# main-stm-03_1.net
KiCad netlist of a schematic drawn in EAGLE
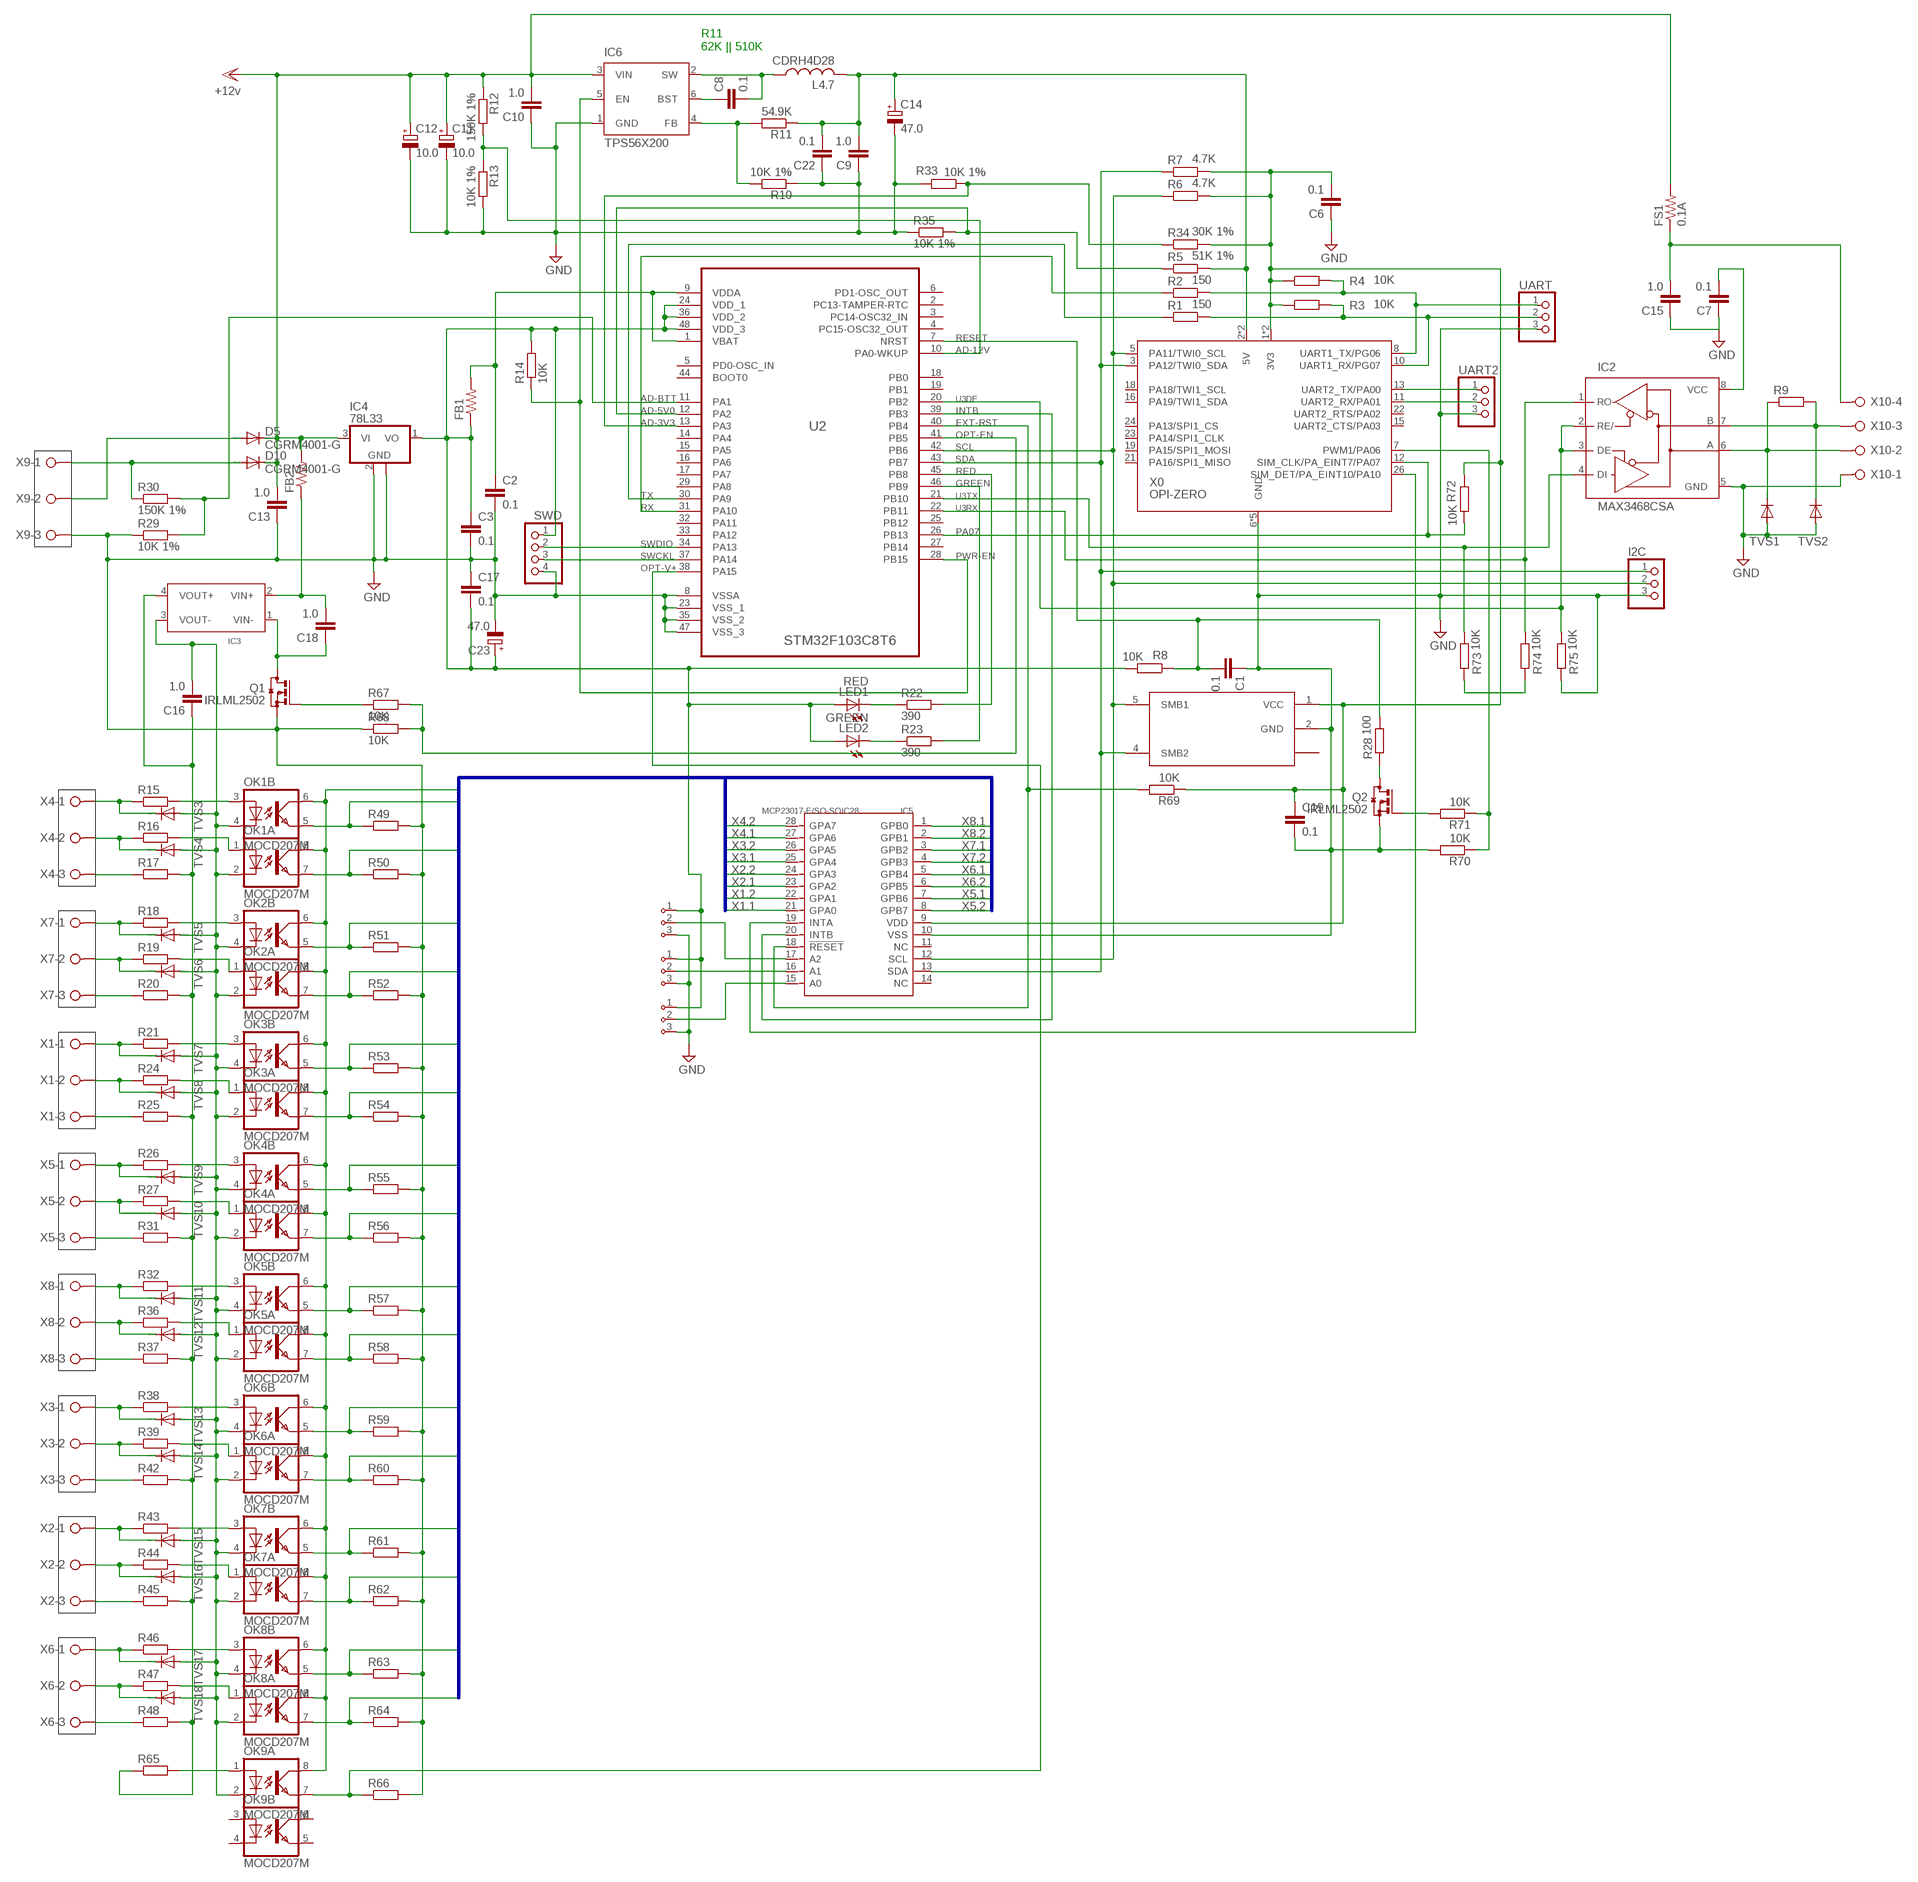
[diagram p0: schematic, sheet 1]

(export (version "E")
  (design (tool "Eeschema 10.0.6"))
  (components
    (comp (ref "A0")
      (value "ADDR3PIN0603")
      (footprint "eagle-import:0603-3PIN")
      (libsource (lib "eagle-import") (part "ADDR3PIN0603"))
    )
    (comp (ref "A1")
      (value "ADDR3PIN0603")
      (footprint "eagle-import:0603-3PIN")
      (libsource (lib "eagle-import") (part "ADDR3PIN0603"))
    )
    (comp (ref "A2")
      (value "ADDR3PIN0603")
      (footprint "eagle-import:0603-3PIN")
      (libsource (lib "eagle-import") (part "ADDR3PIN0603"))
    )
    (comp (ref "C1")
      (value "0.1")
      (footprint "eagle-import:C0603")
      (libsource (lib "eagle-import") (part "C-EUC0603"))
    )
    (comp (ref "C2")
      (value "0.1")
      (footprint "eagle-import:C0603")
      (libsource (lib "eagle-import") (part "C-EUC0603"))
    )
    (comp (ref "C3")
      (value "0.1")
      (footprint "eagle-import:C0603")
      (libsource (lib "eagle-import") (part "C-EUC0603"))
    )
    (comp (ref "C6")
      (value "0.1")
      (footprint "eagle-import:C0805")
      (libsource (lib "eagle-import") (part "C-EUC0805"))
    )
    (comp (ref "C7")
      (value "0.1")
      (footprint "eagle-import:C0805")
      (libsource (lib "eagle-import") (part "C-EUC0805"))
    )
    (comp (ref "C8")
      (value "0.1")
      (footprint "eagle-import:C0805")
      (libsource (lib "eagle-import") (part "C-EUC0805"))
    )
    (comp (ref "C9")
      (value "1.0")
      (footprint "eagle-import:C0805")
      (libsource (lib "eagle-import") (part "C-EUC0805"))
    )
    (comp (ref "C10")
      (value "1.0")
      (footprint "eagle-import:C1206")
      (libsource (lib "eagle-import") (part "C-EUC1206"))
    )
    (comp (ref "C11")
      (value "10.0")
      (footprint "eagle-import:C_6032-28R")
      (libsource (lib "eagle-import") (part "CPOL-EUC/6032-28R"))
    )
    (comp (ref "C12")
      (value "10.0")
      (footprint "eagle-import:C_6032-28R")
      (libsource (lib "eagle-import") (part "CPOL-EUC/6032-28R"))
    )
    (comp (ref "C13")
      (value "1.0")
      (footprint "eagle-import:C1206")
      (libsource (lib "eagle-import") (part "C-EUC1206"))
    )
    (comp (ref "C14")
      (value "47.0")
      (footprint "eagle-import:B_3528-21R")
      (libsource (lib "eagle-import") (part "CPOL-EUB/3528-21R"))
    )
    (comp (ref "C15")
      (value "1.0")
      (footprint "eagle-import:C1206")
      (libsource (lib "eagle-import") (part "C-EUC1206"))
    )
    (comp (ref "C16")
      (value "1.0")
      (footprint "eagle-import:C1206")
      (libsource (lib "eagle-import") (part "C-EUC1206"))
    )
    (comp (ref "C17")
      (value "0.1")
      (footprint "eagle-import:C0603")
      (libsource (lib "eagle-import") (part "C-EUC0603"))
    )
    (comp (ref "C18")
      (value "1.0")
      (footprint "eagle-import:C1206")
      (libsource (lib "eagle-import") (part "C-EUC1206"))
    )
    (comp (ref "C19")
      (value "0.1")
      (footprint "eagle-import:C0603")
      (libsource (lib "eagle-import") (part "C-EUC0603"))
    )
    (comp (ref "C22")
      (value "0.1")
      (footprint "eagle-import:C0805")
      (libsource (lib "eagle-import") (part "C-EUC0805"))
    )
    (comp (ref "C23")
      (value "47.0")
      (footprint "eagle-import:B_3528-21R")
      (libsource (lib "eagle-import") (part "CPOL-EUB/3528-21R"))
    )
    (comp (ref "D5")
      (value "CGRM4001-G")
      (footprint "eagle-import:SOD-123_MINI-SMA")
      (libsource (lib "eagle-import") (part "CGRM400-G1"))
    )
    (comp (ref "D10")
      (value "CGRM4001-G")
      (footprint "eagle-import:SOD-123_MINI-SMA")
      (libsource (lib "eagle-import") (part "CGRM400-G1"))
    )
    (comp (ref "FB1")
      (value "R-US_R0805")
      (footprint "eagle-import:R0805")
      (libsource (lib "eagle-import") (part "R-US_R0805"))
    )
    (comp (ref "FB2")
      (value "R-US_R1206")
      (footprint "eagle-import:R1206")
      (libsource (lib "eagle-import") (part "R-US_R1206"))
    )
    (comp (ref "FS1")
      (value "0.1A")
      (footprint "eagle-import:R1210")
      (libsource (lib "eagle-import") (part "R-US_R1210"))
    )
    (comp (ref "I2C")
      (value "PINHD-1X3")
      (footprint "eagle-import:1X03")
      (libsource (lib "eagle-import") (part "PINHD-1X3"))
    )
    (comp (ref "IC2")
      (value "MAX3468CSA")
      (footprint "eagle-import:SO08")
      (fields (field (name "MPN") "MAX3468CSA+"))
      (libsource (lib "eagle-import") (part "MAX34SA68C"))
    )
    (comp (ref "IC3")
      (value "DC-DC-CONV-4PIN-ISOLATINGMURATA-NME-05-12-SERIES")
      (footprint "eagle-import:DC-DC-MURATA-NME-05-12-SERIES")
      (libsource (lib "eagle-import") (part "DC-DC-CONV-4PIN-ISOLATINGMURATA-NME-05-12-SERIES"))
    )
    (comp (ref "IC4")
      (value "78L33")
      (footprint "eagle-import:SOT89")
      (libsource (lib "eagle-import") (part "78LF05"))
    )
    (comp (ref "IC5")
      (value "MCP23017-E/SO-SOIC28")
      (footprint "eagle-import:SOIC28-1.27-17.9X7.5MM")
      (fields (field (name "MPN") "MCP23017-E/SO"))
      (libsource (lib "eagle-import") (part "INTERFACE-MCP23017-E(SOIC28)"))
    )
    (comp (ref "IC6")
      (value "TPS56X200")
      (footprint "eagle-import:TSOT23-6_DDC")
      (libsource (lib "eagle-import") (part "TPS56X200"))
    )
    (comp (ref "IC7")
      (value "LTC1694")
      (footprint "eagle-import:SOT23-5")
      (libsource (lib "eagle-import") (part "LTC1694"))
    )
    (comp (ref "L4.7")
      (value "CDRH4D28")
      (footprint "eagle-import:CDRH4D28")
      (libsource (lib "eagle-import") (part "CDRH4D28"))
    )
    (comp (ref "LED1")
      (value "RED")
      (footprint "eagle-import:CHIPLED_1206")
      (libsource (lib "eagle-import") (part "LEDCHIPLED_1206"))
    )
    (comp (ref "LED2")
      (value "GREEN")
      (footprint "eagle-import:CHIPLED_1206")
      (libsource (lib "eagle-import") (part "LEDCHIPLED_1206"))
    )
    (comp (ref "OK1")
      (value "MOCD207M")
      (footprint "eagle-import:SOIC08-FAIRCHILD")
      (fields (field (name "MF") "FAIRCHILD SEMICONDUCTOR") (field (name "MPN") "MOCD207-M"))
      (libsource (lib "eagle-import") (part "MOCD20M7"))
    )
    (comp (ref "OK2")
      (value "MOCD207M")
      (footprint "eagle-import:SOIC08-FAIRCHILD")
      (fields (field (name "MF") "FAIRCHILD SEMICONDUCTOR") (field (name "MPN") "MOCD207-M"))
      (libsource (lib "eagle-import") (part "MOCD20M7"))
    )
    (comp (ref "OK3")
      (value "MOCD207M")
      (footprint "eagle-import:SOIC08-FAIRCHILD")
      (fields (field (name "MF") "FAIRCHILD SEMICONDUCTOR") (field (name "MPN") "MOCD207-M"))
      (libsource (lib "eagle-import") (part "MOCD20M7"))
    )
    (comp (ref "OK4")
      (value "MOCD207M")
      (footprint "eagle-import:SOIC08-FAIRCHILD")
      (fields (field (name "MF") "FAIRCHILD SEMICONDUCTOR") (field (name "MPN") "MOCD207-M"))
      (libsource (lib "eagle-import") (part "MOCD20M7"))
    )
    (comp (ref "OK5")
      (value "MOCD207M")
      (footprint "eagle-import:SOIC08-FAIRCHILD")
      (fields (field (name "MF") "FAIRCHILD SEMICONDUCTOR") (field (name "MPN") "MOCD207-M"))
      (libsource (lib "eagle-import") (part "MOCD20M7"))
    )
    (comp (ref "OK6")
      (value "MOCD207M")
      (footprint "eagle-import:SOIC08-FAIRCHILD")
      (fields (field (name "MF") "FAIRCHILD SEMICONDUCTOR") (field (name "MPN") "MOCD207-M"))
      (libsource (lib "eagle-import") (part "MOCD20M7"))
    )
    (comp (ref "OK7")
      (value "MOCD207M")
      (footprint "eagle-import:SOIC08-FAIRCHILD")
      (fields (field (name "MF") "FAIRCHILD SEMICONDUCTOR") (field (name "MPN") "MOCD207-M"))
      (libsource (lib "eagle-import") (part "MOCD20M7"))
    )
    (comp (ref "OK8")
      (value "MOCD207M")
      (footprint "eagle-import:SOIC08-FAIRCHILD")
      (fields (field (name "MF") "FAIRCHILD SEMICONDUCTOR") (field (name "MPN") "MOCD207-M"))
      (libsource (lib "eagle-import") (part "MOCD20M7"))
    )
    (comp (ref "OK9")
      (value "MOCD207M")
      (footprint "eagle-import:SOIC08-FAIRCHILD")
      (fields (field (name "MF") "FAIRCHILD SEMICONDUCTOR") (field (name "MPN") "MOCD207-M"))
      (libsource (lib "eagle-import") (part "MOCD20M7"))
    )
    (comp (ref "Q1")
      (value "IRLML2502")
      (footprint "eagle-import:SOT23")
      (libsource (lib "eagle-import") (part "IRLML2502"))
    )
    (comp (ref "Q2")
      (value "IRLML2502")
      (footprint "eagle-import:SOT23")
      (libsource (lib "eagle-import") (part "IRLML2502"))
    )
    (comp (ref "R1")
      (value "150")
      (footprint "eagle-import:R0603")
      (libsource (lib "eagle-import") (part "R-EU_R0603"))
    )
    (comp (ref "R2")
      (value "150")
      (footprint "eagle-import:R0603")
      (libsource (lib "eagle-import") (part "R-EU_R0603"))
    )
    (comp (ref "R3")
      (value "10K")
      (footprint "eagle-import:R0603")
      (libsource (lib "eagle-import") (part "R-EU_R0603"))
    )
    (comp (ref "R4")
      (value "10K")
      (footprint "eagle-import:R0603")
      (libsource (lib "eagle-import") (part "R-EU_R0603"))
    )
    (comp (ref "R5")
      (value "51K 1%")
      (footprint "eagle-import:R0603")
      (libsource (lib "eagle-import") (part "R-EU_R0603"))
    )
    (comp (ref "R6")
      (value "4.7K")
      (footprint "eagle-import:R0603")
      (libsource (lib "eagle-import") (part "R-EU_R0603"))
    )
    (comp (ref "R7")
      (value "4.7K")
      (footprint "eagle-import:R0603")
      (libsource (lib "eagle-import") (part "R-EU_R0603"))
    )
    (comp (ref "R8")
      (value "10K")
      (footprint "eagle-import:R0603")
      (libsource (lib "eagle-import") (part "R-EU_R0603"))
    )
    (comp (ref "R9")
      (value "R-EU_R1206")
      (footprint "eagle-import:R1206")
      (libsource (lib "eagle-import") (part "R-EU_R1206"))
    )
    (comp (ref "R10")
      (value "10K 1%")
      (footprint "eagle-import:R0603")
      (libsource (lib "eagle-import") (part "R-EU_R0603"))
    )
    (comp (ref "R11")
      (value "54.9K")
      (footprint "eagle-import:R0603")
      (libsource (lib "eagle-import") (part "R-EU_R0603"))
    )
    (comp (ref "R12")
      (value "150K 1%")
      (footprint "eagle-import:R0603")
      (libsource (lib "eagle-import") (part "R-EU_R0603"))
    )
    (comp (ref "R13")
      (value "10K 1%")
      (footprint "eagle-import:R0603")
      (libsource (lib "eagle-import") (part "R-EU_R0603"))
    )
    (comp (ref "R14")
      (value "10K")
      (footprint "eagle-import:R0603")
      (libsource (lib "eagle-import") (part "R-EU_R0603"))
    )
    (comp (ref "R15")
      (value "R-EU_R0603")
      (footprint "eagle-import:R0603")
      (libsource (lib "eagle-import") (part "R-EU_R0603"))
    )
    (comp (ref "R16")
      (value "R-EU_R0603")
      (footprint "eagle-import:R0603")
      (libsource (lib "eagle-import") (part "R-EU_R0603"))
    )
    (comp (ref "R17")
      (value "R-EU_R0603")
      (footprint "eagle-import:R0603")
      (libsource (lib "eagle-import") (part "R-EU_R0603"))
    )
    (comp (ref "R18")
      (value "R-EU_R0603")
      (footprint "eagle-import:R0603")
      (libsource (lib "eagle-import") (part "R-EU_R0603"))
    )
    (comp (ref "R19")
      (value "R-EU_R0603")
      (footprint "eagle-import:R0603")
      (libsource (lib "eagle-import") (part "R-EU_R0603"))
    )
    (comp (ref "R20")
      (value "R-EU_R0603")
      (footprint "eagle-import:R0603")
      (libsource (lib "eagle-import") (part "R-EU_R0603"))
    )
    (comp (ref "R21")
      (value "R-EU_R0603")
      (footprint "eagle-import:R0603")
      (libsource (lib "eagle-import") (part "R-EU_R0603"))
    )
    (comp (ref "R22")
      (value "390")
      (footprint "eagle-import:R0603")
      (libsource (lib "eagle-import") (part "R-EU_R0603"))
    )
    (comp (ref "R23")
      (value "390")
      (footprint "eagle-import:R0603")
      (libsource (lib "eagle-import") (part "R-EU_R0603"))
    )
    (comp (ref "R24")
      (value "R-EU_R0603")
      (footprint "eagle-import:R0603")
      (libsource (lib "eagle-import") (part "R-EU_R0603"))
    )
    (comp (ref "R25")
      (value "R-EU_R0603")
      (footprint "eagle-import:R0603")
      (libsource (lib "eagle-import") (part "R-EU_R0603"))
    )
    (comp (ref "R26")
      (value "R-EU_R0603")
      (footprint "eagle-import:R0603")
      (libsource (lib "eagle-import") (part "R-EU_R0603"))
    )
    (comp (ref "R27")
      (value "R-EU_R0603")
      (footprint "eagle-import:R0603")
      (libsource (lib "eagle-import") (part "R-EU_R0603"))
    )
    (comp (ref "R28")
      (value "100")
      (footprint "eagle-import:R0603")
      (libsource (lib "eagle-import") (part "R-EU_R0603"))
    )
    (comp (ref "R29")
      (value "10K 1%")
      (footprint "eagle-import:R0603")
      (libsource (lib "eagle-import") (part "R-EU_R0603"))
    )
    (comp (ref "R30")
      (value "150K 1%")
      (footprint "eagle-import:R0603")
      (libsource (lib "eagle-import") (part "R-EU_R0603"))
    )
    (comp (ref "R31")
      (value "R-EU_R0603")
      (footprint "eagle-import:R0603")
      (libsource (lib "eagle-import") (part "R-EU_R0603"))
    )
    (comp (ref "R32")
      (value "R-EU_R0603")
      (footprint "eagle-import:R0603")
      (libsource (lib "eagle-import") (part "R-EU_R0603"))
    )
    (comp (ref "R33")
      (value "10K 1%")
      (footprint "eagle-import:R0603")
      (libsource (lib "eagle-import") (part "R-EU_R0603"))
    )
    (comp (ref "R34")
      (value "30K 1%")
      (footprint "eagle-import:R0603")
      (libsource (lib "eagle-import") (part "R-EU_R0603"))
    )
    (comp (ref "R35")
      (value "10K 1%")
      (footprint "eagle-import:R0603")
      (libsource (lib "eagle-import") (part "R-EU_R0603"))
    )
    (comp (ref "R36")
      (value "R-EU_R0603")
      (footprint "eagle-import:R0603")
      (libsource (lib "eagle-import") (part "R-EU_R0603"))
    )
    (comp (ref "R37")
      (value "R-EU_R0603")
      (footprint "eagle-import:R0603")
      (libsource (lib "eagle-import") (part "R-EU_R0603"))
    )
    (comp (ref "R38")
      (value "R-EU_R0603")
      (footprint "eagle-import:R0603")
      (libsource (lib "eagle-import") (part "R-EU_R0603"))
    )
    (comp (ref "R39")
      (value "R-EU_R0603")
      (footprint "eagle-import:R0603")
      (libsource (lib "eagle-import") (part "R-EU_R0603"))
    )
    (comp (ref "R42")
      (value "R-EU_R0603")
      (footprint "eagle-import:R0603")
      (libsource (lib "eagle-import") (part "R-EU_R0603"))
    )
    (comp (ref "R43")
      (value "R-EU_R0603")
      (footprint "eagle-import:R0603")
      (libsource (lib "eagle-import") (part "R-EU_R0603"))
    )
    (comp (ref "R44")
      (value "R-EU_R0603")
      (footprint "eagle-import:R0603")
      (libsource (lib "eagle-import") (part "R-EU_R0603"))
    )
    (comp (ref "R45")
      (value "R-EU_R0603")
      (footprint "eagle-import:R0603")
      (libsource (lib "eagle-import") (part "R-EU_R0603"))
    )
    (comp (ref "R46")
      (value "R-EU_R0603")
      (footprint "eagle-import:R0603")
      (libsource (lib "eagle-import") (part "R-EU_R0603"))
    )
    (comp (ref "R47")
      (value "R-EU_R0603")
      (footprint "eagle-import:R0603")
      (libsource (lib "eagle-import") (part "R-EU_R0603"))
    )
    (comp (ref "R48")
      (value "R-EU_R0603")
      (footprint "eagle-import:R0603")
      (libsource (lib "eagle-import") (part "R-EU_R0603"))
    )
    (comp (ref "R49")
      (value "R-EU_R0603")
      (footprint "eagle-import:R0603")
      (libsource (lib "eagle-import") (part "R-EU_R0603"))
    )
    (comp (ref "R50")
      (value "R-EU_R0603")
      (footprint "eagle-import:R0603")
      (libsource (lib "eagle-import") (part "R-EU_R0603"))
    )
    (comp (ref "R51")
      (value "R-EU_R0603")
      (footprint "eagle-import:R0603")
      (libsource (lib "eagle-import") (part "R-EU_R0603"))
    )
    (comp (ref "R52")
      (value "R-EU_R0603")
      (footprint "eagle-import:R0603")
      (libsource (lib "eagle-import") (part "R-EU_R0603"))
    )
    (comp (ref "R53")
      (value "R-EU_R0603")
      (footprint "eagle-import:R0603")
      (libsource (lib "eagle-import") (part "R-EU_R0603"))
    )
    (comp (ref "R54")
      (value "R-EU_R0603")
      (footprint "eagle-import:R0603")
      (libsource (lib "eagle-import") (part "R-EU_R0603"))
    )
    (comp (ref "R55")
      (value "R-EU_R0603")
      (footprint "eagle-import:R0603")
      (libsource (lib "eagle-import") (part "R-EU_R0603"))
    )
    (comp (ref "R56")
      (value "R-EU_R0603")
      (footprint "eagle-import:R0603")
      (libsource (lib "eagle-import") (part "R-EU_R0603"))
    )
    (comp (ref "R57")
      (value "R-EU_R0603")
      (footprint "eagle-import:R0603")
      (libsource (lib "eagle-import") (part "R-EU_R0603"))
    )
    (comp (ref "R58")
      (value "R-EU_R0603")
      (footprint "eagle-import:R0603")
      (libsource (lib "eagle-import") (part "R-EU_R0603"))
    )
    (comp (ref "R59")
      (value "R-EU_R0603")
      (footprint "eagle-import:R0603")
      (libsource (lib "eagle-import") (part "R-EU_R0603"))
    )
    (comp (ref "R60")
      (value "R-EU_R0603")
      (footprint "eagle-import:R0603")
      (libsource (lib "eagle-import") (part "R-EU_R0603"))
    )
    (comp (ref "R61")
      (value "R-EU_R0603")
      (footprint "eagle-import:R0603")
      (libsource (lib "eagle-import") (part "R-EU_R0603"))
    )
    (comp (ref "R62")
      (value "R-EU_R0603")
      (footprint "eagle-import:R0603")
      (libsource (lib "eagle-import") (part "R-EU_R0603"))
    )
    (comp (ref "R63")
      (value "R-EU_R0603")
      (footprint "eagle-import:R0603")
      (libsource (lib "eagle-import") (part "R-EU_R0603"))
    )
    (comp (ref "R64")
      (value "R-EU_R0603")
      (footprint "eagle-import:R0603")
      (libsource (lib "eagle-import") (part "R-EU_R0603"))
    )
    (comp (ref "R65")
      (value "R-EU_R0603")
      (footprint "eagle-import:R0603")
      (libsource (lib "eagle-import") (part "R-EU_R0603"))
    )
    (comp (ref "R66")
      (value "R-EU_R0603")
      (footprint "eagle-import:R0603")
      (libsource (lib "eagle-import") (part "R-EU_R0603"))
    )
    (comp (ref "R67")
      (value "10K")
      (footprint "eagle-import:R0603")
      (libsource (lib "eagle-import") (part "R-EU_R0603"))
    )
    (comp (ref "R68")
      (value "10K")
      (footprint "eagle-import:R0603")
      (libsource (lib "eagle-import") (part "R-EU_R0603"))
    )
    (comp (ref "R69")
      (value "10K")
      (footprint "eagle-import:R0603")
      (libsource (lib "eagle-import") (part "R-EU_R0603"))
    )
    (comp (ref "R70")
      (value "10K")
      (footprint "eagle-import:R0603")
      (libsource (lib "eagle-import") (part "R-EU_R0603"))
    )
    (comp (ref "R71")
      (value "10K")
      (footprint "eagle-import:R0603")
      (libsource (lib "eagle-import") (part "R-EU_R0603"))
    )
    (comp (ref "R72")
      (value "10K")
      (footprint "eagle-import:R0603")
      (libsource (lib "eagle-import") (part "R-EU_R0603"))
    )
    (comp (ref "R73")
      (value "10K")
      (footprint "eagle-import:R0603")
      (libsource (lib "eagle-import") (part "R-EU_R0603"))
    )
    (comp (ref "R74")
      (value "10K")
      (footprint "eagle-import:R0603")
      (libsource (lib "eagle-import") (part "R-EU_R0603"))
    )
    (comp (ref "R75")
      (value "10K")
      (footprint "eagle-import:R0603")
      (libsource (lib "eagle-import") (part "R-EU_R0603"))
    )
    (comp (ref "SWD")
      (value "PINHD-1X4")
      (footprint "eagle-import:1X04")
      (libsource (lib "eagle-import") (part "PINHD-1X4"))
    )
    (comp (ref "TVS1")
      (value "DIODE-SOD323-W")
      (footprint "eagle-import:SOD323-W")
      (libsource (lib "eagle-import") (part "DIODE-SOD323-W"))
    )
    (comp (ref "TVS2")
      (value "DIODE-SOD323-W")
      (footprint "eagle-import:SOD323-W")
      (libsource (lib "eagle-import") (part "DIODE-SOD323-W"))
    )
    (comp (ref "TVS3")
      (value "DIODE-SOD323-W")
      (footprint "eagle-import:SOD323-W")
      (libsource (lib "eagle-import") (part "DIODE-SOD323-W"))
    )
    (comp (ref "TVS4")
      (value "DIODE-SOD323-W")
      (footprint "eagle-import:SOD323-W")
      (libsource (lib "eagle-import") (part "DIODE-SOD323-W"))
    )
    (comp (ref "TVS5")
      (value "DIODE-SOD323-W")
      (footprint "eagle-import:SOD323-W")
      (libsource (lib "eagle-import") (part "DIODE-SOD323-W"))
    )
    (comp (ref "TVS6")
      (value "DIODE-SOD323-W")
      (footprint "eagle-import:SOD323-W")
      (libsource (lib "eagle-import") (part "DIODE-SOD323-W"))
    )
    (comp (ref "TVS7")
      (value "DIODE-SOD323-W")
      (footprint "eagle-import:SOD323-W")
      (libsource (lib "eagle-import") (part "DIODE-SOD323-W"))
    )
    (comp (ref "TVS8")
      (value "DIODE-SOD323-W")
      (footprint "eagle-import:SOD323-W")
      (libsource (lib "eagle-import") (part "DIODE-SOD323-W"))
    )
    (comp (ref "TVS9")
      (value "DIODE-SOD323-W")
      (footprint "eagle-import:SOD323-W")
      (libsource (lib "eagle-import") (part "DIODE-SOD323-W"))
    )
    (comp (ref "TVS10")
      (value "DIODE-SOD323-W")
      (footprint "eagle-import:SOD323-W")
      (libsource (lib "eagle-import") (part "DIODE-SOD323-W"))
    )
    (comp (ref "TVS11")
      (value "DIODE-SOD323-W")
      (footprint "eagle-import:SOD323-W")
      (libsource (lib "eagle-import") (part "DIODE-SOD323-W"))
    )
    (comp (ref "TVS12")
      (value "DIODE-SOD323-W")
      (footprint "eagle-import:SOD323-W")
      (libsource (lib "eagle-import") (part "DIODE-SOD323-W"))
    )
    (comp (ref "TVS13")
      (value "DIODE-SOD323-W")
      (footprint "eagle-import:SOD323-W")
      (libsource (lib "eagle-import") (part "DIODE-SOD323-W"))
    )
    (comp (ref "TVS14")
      (value "DIODE-SOD323-W")
      (footprint "eagle-import:SOD323-W")
      (libsource (lib "eagle-import") (part "DIODE-SOD323-W"))
    )
    (comp (ref "TVS15")
      (value "DIODE-SOD323-W")
      (footprint "eagle-import:SOD323-W")
      (libsource (lib "eagle-import") (part "DIODE-SOD323-W"))
    )
    (comp (ref "TVS16")
      (value "DIODE-SOD323-W")
      (footprint "eagle-import:SOD323-W")
      (libsource (lib "eagle-import") (part "DIODE-SOD323-W"))
    )
    (comp (ref "TVS17")
      (value "DIODE-SOD323-W")
      (footprint "eagle-import:SOD323-W")
      (libsource (lib "eagle-import") (part "DIODE-SOD323-W"))
    )
    (comp (ref "TVS18")
      (value "DIODE-SOD323-W")
      (footprint "eagle-import:SOD323-W")
      (libsource (lib "eagle-import") (part "DIODE-SOD323-W"))
    )
    (comp (ref "U2")
      (value "STM32F103C8T6")
      (footprint "eagle-import:QFP50P900X900X160-48N")
      (fields (field (name "MPN") "STM32F100CBT6B"))
      (libsource (lib "eagle-import") (part "STM32F100CBT6B"))
    )
    (comp (ref "UART")
      (value "PINHD-1X3")
      (footprint "eagle-import:1X03")
      (libsource (lib "eagle-import") (part "PINHD-1X3"))
    )
    (comp (ref "UART2")
      (value "PINHD-1X3")
      (footprint "eagle-import:1X03")
      (libsource (lib "eagle-import") (part "PINHD-1X3"))
    )
    (comp (ref "X0")
      (value "OPI-ZERO")
      (footprint "eagle-import:OPI0")
      (libsource (lib "eagle-import") (part "OPI-ZERO"))
    )
    (comp (ref "X1")
      (value "W237-03P")
      (footprint "eagle-import:W237-133")
      (libsource (lib "eagle-import") (part "W237-03P"))
    )
    (comp (ref "X2")
      (value "W237-03P")
      (footprint "eagle-import:W237-133")
      (libsource (lib "eagle-import") (part "W237-03P"))
    )
    (comp (ref "X3")
      (value "W237-03P")
      (footprint "eagle-import:W237-133")
      (libsource (lib "eagle-import") (part "W237-03P"))
    )
    (comp (ref "X4")
      (value "W237-03P")
      (footprint "eagle-import:W237-133")
      (libsource (lib "eagle-import") (part "W237-03P"))
    )
    (comp (ref "X5")
      (value "W237-03P")
      (footprint "eagle-import:W237-133")
      (libsource (lib "eagle-import") (part "W237-03P"))
    )
    (comp (ref "X6")
      (value "W237-03P")
      (footprint "eagle-import:W237-133")
      (libsource (lib "eagle-import") (part "W237-03P"))
    )
    (comp (ref "X7")
      (value "W237-03P")
      (footprint "eagle-import:W237-133")
      (libsource (lib "eagle-import") (part "W237-03P"))
    )
    (comp (ref "X8")
      (value "W237-03P")
      (footprint "eagle-import:W237-133")
      (libsource (lib "eagle-import") (part "W237-03P"))
    )
    (comp (ref "X9")
      (value "W237-03P")
      (footprint "eagle-import:W237-133")
      (libsource (lib "eagle-import") (part "W237-03P"))
    )
    (comp (ref "X10")
      (value "W237-04P")
      (footprint "eagle-import:W237-4P")
      (libsource (lib "eagle-import") (part "W237-04P"))
    )
  )
  (nets
    (net (code "1") (name "+12v") (class "Default")
      (node (ref "C10") (pin "2") (pinfunction "2_2") (pintype "passive"))
      (node (ref "C11") (pin "+") (pinfunction "+_+") (pintype "passive"))
      (node (ref "C12") (pin "+") (pinfunction "+_+") (pintype "passive"))
      (node (ref "C13") (pin "2") (pinfunction "2_2") (pintype "passive"))
      (node (ref "D10") (pin "C") (pinfunction "C_C") (pintype "passive"))
      (node (ref "D5") (pin "C") (pinfunction "C_C") (pintype "passive"))
      (node (ref "FB2") (pin "2") (pinfunction "2_2") (pintype "passive"))
      (node (ref "FS1") (pin "2") (pinfunction "2_2") (pintype "passive"))
      (node (ref "IC4") (pin "3") (pinfunction "VI_3") (pintype "input"))
      (node (ref "IC6") (pin "3") (pinfunction "VIN_3") (pintype "input"))
      (node (ref "R12") (pin "1") (pinfunction "1_1") (pintype "passive"))
    )
    (net (code "2") (name "/AD-3V3") (class "Default")
      (node (ref "R33") (pin "1") (pinfunction "1_1") (pintype "passive"))
      (node (ref "R34") (pin "1") (pinfunction "1_1") (pintype "passive"))
      (node (ref "U2") (pin "13") (pinfunction "PA3_13") (pintype "bidirectional"))
    )
    (net (code "3") (name "/AD-5V0") (class "Default")
      (node (ref "R35") (pin "2") (pinfunction "2_2") (pintype "passive"))
      (node (ref "R5") (pin "1") (pinfunction "1_1") (pintype "passive"))
      (node (ref "U2") (pin "12") (pinfunction "PA2_12") (pintype "bidirectional"))
    )
    (net (code "4") (name "/AD-12V") (class "Default")
      (node (ref "R12") (pin "2") (pinfunction "2_2") (pintype "passive"))
      (node (ref "R13") (pin "1") (pinfunction "1_1") (pintype "passive"))
      (node (ref "U2") (pin "10") (pinfunction "PA0-WKUP_10") (pintype "bidirectional"))
    )
    (net (code "5") (name "/AD-BTT") (class "Default")
      (node (ref "R29") (pin "2") (pinfunction "2_2") (pintype "passive"))
      (node (ref "R30") (pin "2") (pinfunction "2_2") (pintype "passive"))
      (node (ref "U2") (pin "11") (pinfunction "PA1_11") (pintype "bidirectional"))
    )
    (net (code "6") (name "/EXT-RST") (class "Default")
      (node (ref "IC5") (pin "18") (pinfunction "~{RESET}_18") (pintype "bidirectional"))
      (node (ref "R69") (pin "2") (pinfunction "2_2") (pintype "passive"))
      (node (ref "U2") (pin "40") (pinfunction "PB4_40") (pintype "bidirectional"))
    )
    (net (code "7") (name "/GREEN") (class "Default")
      (node (ref "R23") (pin "2") (pinfunction "2_2") (pintype "passive"))
      (node (ref "U2") (pin "46") (pinfunction "PB9_46") (pintype "bidirectional"))
    )
    (net (code "8") (name "/INTB") (class "Default")
      (node (ref "IC5") (pin "20") (pinfunction "INTB_20") (pintype "bidirectional"))
      (node (ref "U2") (pin "39") (pinfunction "PB3_39") (pintype "bidirectional"))
    )
    (net (code "9") (name "/OPT-EN") (class "Default")
      (node (ref "R67") (pin "2") (pinfunction "2_2") (pintype "passive"))
      (node (ref "R68") (pin "2") (pinfunction "2_2") (pintype "passive"))
      (node (ref "U2") (pin "41") (pinfunction "PB5_41") (pintype "bidirectional"))
    )
    (net (code "10") (name "/OPT-V+") (class "Default")
      (node (ref "OK9") (pin "7") (pinfunction "EMIT_7") (pintype "passive"))
      (node (ref "R66") (pin "1") (pinfunction "1_1") (pintype "passive"))
      (node (ref "U2") (pin "38") (pinfunction "PA15_38") (pintype "bidirectional"))
    )
    (net (code "11") (name "/PA07") (class "Default")
      (node (ref "R72") (pin "2") (pinfunction "2_2") (pintype "passive"))
      (node (ref "U2") (pin "26") (pinfunction "PB13_26") (pintype "bidirectional"))
      (node (ref "X0") (pin "12") (pinfunction "SIM_CLK/PA_EINT7/PA07_12") (pintype "bidirectional"))
    )
    (net (code "12") (name "/PWR-EN") (class "Default")
      (node (ref "IC6") (pin "5") (pinfunction "EN_5") (pintype "input"))
      (node (ref "R14") (pin "1") (pinfunction "1_1") (pintype "passive"))
      (node (ref "U2") (pin "28") (pinfunction "PB15_28") (pintype "bidirectional"))
    )
    (net (code "13") (name "/RED") (class "Default")
      (node (ref "R22") (pin "2") (pinfunction "2_2") (pintype "passive"))
      (node (ref "U2") (pin "45") (pinfunction "PB8_45") (pintype "bidirectional"))
    )
    (net (code "14") (name "/RESET") (class "Default")
      (node (ref "C1") (pin "2") (pinfunction "2_2") (pintype "passive"))
      (node (ref "R28") (pin "2") (pinfunction "2_2") (pintype "passive"))
      (node (ref "R8") (pin "1") (pinfunction "1_1") (pintype "passive"))
      (node (ref "U2") (pin "7") (pinfunction "NRST_7") (pintype "bidirectional"))
    )
    (net (code "15") (name "/RX") (class "Default")
      (node (ref "R2") (pin "1") (pinfunction "1_1") (pintype "passive"))
      (node (ref "U2") (pin "31") (pinfunction "PA10_31") (pintype "bidirectional"))
    )
    (net (code "16") (name "/SCL") (class "Default")
      (node (ref "I2C") (pin "2") (pinfunction "2_2") (pintype "passive"))
      (node (ref "IC5") (pin "12") (pinfunction "SCL_12") (pintype "bidirectional"))
      (node (ref "IC7") (pin "5") (pinfunction "SMB1_5") (pintype "bidirectional"))
      (node (ref "R6") (pin "1") (pinfunction "1_1") (pintype "passive"))
      (node (ref "U2") (pin "42") (pinfunction "PB6_42") (pintype "bidirectional"))
      (node (ref "X0") (pin "5") (pinfunction "PA11/TWI0_SCL_5") (pintype "bidirectional"))
    )
    (net (code "17") (name "/SDA") (class "Default")
      (node (ref "I2C") (pin "1") (pinfunction "1_1") (pintype "passive"))
      (node (ref "IC5") (pin "13") (pinfunction "SDA_13") (pintype "bidirectional"))
      (node (ref "IC7") (pin "4") (pinfunction "SMB2_4") (pintype "bidirectional"))
      (node (ref "R7") (pin "1") (pinfunction "1_1") (pintype "passive"))
      (node (ref "U2") (pin "43") (pinfunction "PB7_43") (pintype "bidirectional"))
      (node (ref "X0") (pin "3") (pinfunction "PA12/TWI0_SDA_3") (pintype "bidirectional"))
    )
    (net (code "18") (name "/SWCKL") (class "Default")
      (node (ref "SWD") (pin "3") (pinfunction "3_3") (pintype "passive"))
      (node (ref "U2") (pin "37") (pinfunction "PA14_37") (pintype "bidirectional"))
    )
    (net (code "19") (name "/SWDIO") (class "Default")
      (node (ref "SWD") (pin "2") (pinfunction "2_2") (pintype "passive"))
      (node (ref "U2") (pin "34") (pinfunction "PA13_34") (pintype "bidirectional"))
    )
    (net (code "20") (name "/TX") (class "Default")
      (node (ref "R1") (pin "1") (pinfunction "1_1") (pintype "passive"))
      (node (ref "U2") (pin "30") (pinfunction "PA9_30") (pintype "bidirectional"))
    )
    (net (code "21") (name "/U3DE") (class "Default")
      (node (ref "IC2") (pin "2") (pinfunction "RE/_2") (pintype "input"))
      (node (ref "IC2") (pin "3") (pinfunction "DE_3") (pintype "input"))
      (node (ref "R75") (pin "2") (pinfunction "2_2") (pintype "passive"))
      (node (ref "U2") (pin "20") (pinfunction "PB2_20") (pintype "bidirectional"))
    )
    (net (code "22") (name "/U3RX") (class "Default")
      (node (ref "IC2") (pin "1") (pinfunction "RO_1") (pintype "output"))
      (node (ref "R74") (pin "2") (pinfunction "2_2") (pintype "passive"))
      (node (ref "U2") (pin "22") (pinfunction "PB11_22") (pintype "bidirectional"))
    )
    (net (code "23") (name "/U3TX") (class "Default")
      (node (ref "IC2") (pin "4") (pinfunction "DI_4") (pintype "input"))
      (node (ref "R73") (pin "2") (pinfunction "2_2") (pintype "passive"))
      (node (ref "U2") (pin "21") (pinfunction "PB10_21") (pintype "bidirectional"))
    )
    (net (code "24") (name "/VCC") (class "Default")
      (node (ref "A0") (pin "1") (pinfunction "P$2_1") (pintype "power_in"))
      (node (ref "A1") (pin "1") (pinfunction "P$2_1") (pintype "power_in"))
      (node (ref "A2") (pin "1") (pinfunction "P$2_1") (pintype "power_in"))
      (node (ref "C17") (pin "2") (pinfunction "2_2") (pintype "passive"))
      (node (ref "C23") (pin "+") (pinfunction "+_+") (pintype "passive"))
      (node (ref "C3") (pin "1") (pinfunction "1_1") (pintype "passive"))
      (node (ref "C7") (pin "2") (pinfunction "2_2") (pintype "passive"))
      (node (ref "FB1") (pin "1") (pinfunction "1_1") (pintype "passive"))
      (node (ref "IC2") (pin "8") (pinfunction "VCC_8") (pintype "power_in"))
      (node (ref "IC4") (pin "1") (pinfunction "VO_1") (pintype "passive"))
      (node (ref "LED1") (pin "A") (pinfunction "A_A") (pintype "passive"))
      (node (ref "LED2") (pin "A") (pinfunction "A_A") (pintype "passive"))
      (node (ref "R14") (pin "2") (pinfunction "2_2") (pintype "passive"))
      (node (ref "R73") (pin "1") (pinfunction "1_1") (pintype "passive"))
      (node (ref "R74") (pin "1") (pinfunction "1_1") (pintype "passive"))
      (node (ref "R8") (pin "2") (pinfunction "2_2") (pintype "passive"))
      (node (ref "SWD") (pin "1") (pinfunction "1_1") (pintype "passive"))
      (node (ref "U2") (pin "24") (pinfunction "VDD_1_24") (pintype "power_in"))
      (node (ref "U2") (pin "36") (pinfunction "VDD_2_36") (pintype "power_in"))
      (node (ref "U2") (pin "48") (pinfunction "VDD_3_48") (pintype "power_in"))
    )
    (net (code "25") (name "/X1.1") (class "Default")
      (node (ref "IC5") (pin "21") (pinfunction "GPA0_21") (pintype "bidirectional"))
      (node (ref "OK3") (pin "5") (pinfunction "EMIT_5") (pintype "passive"))
      (node (ref "R53") (pin "1") (pinfunction "1_1") (pintype "passive"))
    )
    (net (code "26") (name "/X1.2") (class "Default")
      (node (ref "IC5") (pin "22") (pinfunction "GPA1_22") (pintype "bidirectional"))
      (node (ref "OK3") (pin "7") (pinfunction "EMIT_7") (pintype "passive"))
      (node (ref "R54") (pin "1") (pinfunction "1_1") (pintype "passive"))
    )
    (net (code "27") (name "/X2.1") (class "Default")
      (node (ref "IC5") (pin "23") (pinfunction "GPA2_23") (pintype "bidirectional"))
      (node (ref "OK7") (pin "5") (pinfunction "EMIT_5") (pintype "passive"))
      (node (ref "R61") (pin "1") (pinfunction "1_1") (pintype "passive"))
    )
    (net (code "28") (name "/X2.2") (class "Default")
      (node (ref "IC5") (pin "24") (pinfunction "GPA3_24") (pintype "bidirectional"))
      (node (ref "OK7") (pin "7") (pinfunction "EMIT_7") (pintype "passive"))
      (node (ref "R62") (pin "1") (pinfunction "1_1") (pintype "passive"))
    )
    (net (code "29") (name "/X3.1") (class "Default")
      (node (ref "IC5") (pin "25") (pinfunction "GPA4_25") (pintype "bidirectional"))
      (node (ref "OK6") (pin "5") (pinfunction "EMIT_5") (pintype "passive"))
      (node (ref "R59") (pin "1") (pinfunction "1_1") (pintype "passive"))
    )
    (net (code "30") (name "/X3.2") (class "Default")
      (node (ref "IC5") (pin "26") (pinfunction "GPA5_26") (pintype "bidirectional"))
      (node (ref "OK6") (pin "7") (pinfunction "EMIT_7") (pintype "passive"))
      (node (ref "R60") (pin "1") (pinfunction "1_1") (pintype "passive"))
    )
    (net (code "31") (name "/X4.1") (class "Default")
      (node (ref "IC5") (pin "27") (pinfunction "GPA6_27") (pintype "bidirectional"))
      (node (ref "OK1") (pin "5") (pinfunction "EMIT_5") (pintype "passive"))
      (node (ref "R49") (pin "1") (pinfunction "1_1") (pintype "passive"))
    )
    (net (code "32") (name "/X4.2") (class "Default")
      (node (ref "IC5") (pin "28") (pinfunction "GPA7_28") (pintype "bidirectional"))
      (node (ref "OK1") (pin "7") (pinfunction "EMIT_7") (pintype "passive"))
      (node (ref "R50") (pin "1") (pinfunction "1_1") (pintype "passive"))
    )
    (net (code "33") (name "/X5.1") (class "Default")
      (node (ref "IC5") (pin "7") (pinfunction "GPB6_7") (pintype "bidirectional"))
      (node (ref "OK4") (pin "5") (pinfunction "EMIT_5") (pintype "passive"))
      (node (ref "R55") (pin "1") (pinfunction "1_1") (pintype "passive"))
    )
    (net (code "34") (name "/X5.2") (class "Default")
      (node (ref "IC5") (pin "8") (pinfunction "GPB7_8") (pintype "bidirectional"))
      (node (ref "OK4") (pin "7") (pinfunction "EMIT_7") (pintype "passive"))
      (node (ref "R56") (pin "1") (pinfunction "1_1") (pintype "passive"))
    )
    (net (code "35") (name "/X6.1") (class "Default")
      (node (ref "IC5") (pin "5") (pinfunction "GPB4_5") (pintype "bidirectional"))
      (node (ref "OK8") (pin "5") (pinfunction "EMIT_5") (pintype "passive"))
      (node (ref "R63") (pin "1") (pinfunction "1_1") (pintype "passive"))
    )
    (net (code "36") (name "/X6.2") (class "Default")
      (node (ref "IC5") (pin "6") (pinfunction "GPB5_6") (pintype "bidirectional"))
      (node (ref "OK8") (pin "7") (pinfunction "EMIT_7") (pintype "passive"))
      (node (ref "R64") (pin "1") (pinfunction "1_1") (pintype "passive"))
    )
    (net (code "37") (name "/X7.1") (class "Default")
      (node (ref "IC5") (pin "3") (pinfunction "GPB2_3") (pintype "bidirectional"))
      (node (ref "OK2") (pin "5") (pinfunction "EMIT_5") (pintype "passive"))
      (node (ref "R51") (pin "1") (pinfunction "1_1") (pintype "passive"))
    )
    (net (code "38") (name "/X7.2") (class "Default")
      (node (ref "IC5") (pin "4") (pinfunction "GPB3_4") (pintype "bidirectional"))
      (node (ref "OK2") (pin "7") (pinfunction "EMIT_7") (pintype "passive"))
      (node (ref "R52") (pin "1") (pinfunction "1_1") (pintype "passive"))
    )
    (net (code "39") (name "/X8.1") (class "Default")
      (node (ref "IC5") (pin "1") (pinfunction "GPB0_1") (pintype "bidirectional"))
      (node (ref "OK5") (pin "5") (pinfunction "EMIT_5") (pintype "passive"))
      (node (ref "R57") (pin "1") (pinfunction "1_1") (pintype "passive"))
    )
    (net (code "40") (name "/X8.2") (class "Default")
      (node (ref "IC5") (pin "2") (pinfunction "GPB1_2") (pintype "bidirectional"))
      (node (ref "OK5") (pin "7") (pinfunction "EMIT_7") (pintype "passive"))
      (node (ref "R58") (pin "1") (pinfunction "1_1") (pintype "passive"))
    )
    (net (code "41") (name "/Z3V3") (class "Default")
      (node (ref "C19") (pin "1") (pinfunction "1_1") (pintype "passive"))
      (node (ref "C6") (pin "2") (pinfunction "2_2") (pintype "passive"))
      (node (ref "IC5") (pin "9") (pinfunction "VDD_9") (pintype "bidirectional"))
      (node (ref "IC7") (pin "1") (pinfunction "VCC_1") (pintype "power_in"))
      (node (ref "OK1") (pin "6") (pinfunction "COL_6") (pintype "passive"))
      (node (ref "OK1") (pin "8") (pinfunction "COL_8") (pintype "passive"))
      (node (ref "OK2") (pin "6") (pinfunction "COL_6") (pintype "passive"))
      (node (ref "OK2") (pin "8") (pinfunction "COL_8") (pintype "passive"))
      (node (ref "OK3") (pin "6") (pinfunction "COL_6") (pintype "passive"))
      (node (ref "OK3") (pin "8") (pinfunction "COL_8") (pintype "passive"))
      (node (ref "OK4") (pin "6") (pinfunction "COL_6") (pintype "passive"))
      (node (ref "OK4") (pin "8") (pinfunction "COL_8") (pintype "passive"))
      (node (ref "OK5") (pin "6") (pinfunction "COL_6") (pintype "passive"))
      (node (ref "OK5") (pin "8") (pinfunction "COL_8") (pintype "passive"))
      (node (ref "OK6") (pin "6") (pinfunction "COL_6") (pintype "passive"))
      (node (ref "OK6") (pin "8") (pinfunction "COL_8") (pintype "passive"))
      (node (ref "OK7") (pin "6") (pinfunction "COL_6") (pintype "passive"))
      (node (ref "OK7") (pin "8") (pinfunction "COL_8") (pintype "passive"))
      (node (ref "OK8") (pin "6") (pinfunction "COL_6") (pintype "passive"))
      (node (ref "OK8") (pin "8") (pinfunction "COL_8") (pintype "passive"))
      (node (ref "OK9") (pin "8") (pinfunction "COL_8") (pintype "passive"))
      (node (ref "R3") (pin "1") (pinfunction "1_1") (pintype "passive"))
      (node (ref "R34") (pin "2") (pinfunction "2_2") (pintype "passive"))
      (node (ref "R4") (pin "1") (pinfunction "1_1") (pintype "passive"))
      (node (ref "R6") (pin "2") (pinfunction "2_2") (pintype "passive"))
      (node (ref "R69") (pin "1") (pinfunction "1_1") (pintype "passive"))
      (node (ref "R7") (pin "2") (pinfunction "2_2") (pintype "passive"))
      (node (ref "R72") (pin "1") (pinfunction "1_1") (pintype "passive"))
      (node (ref "X0") (pin "1") (pinfunction "3V3_1") (pintype "power_in"))
      (node (ref "X0") (pin "17") (pinfunction "3V3_17") (pintype "power_in"))
    )
    (net (code "42") (name "GND") (class "Default")
      (node (ref "A0") (pin "3") (pinfunction "P$3_3") (pintype "power_in"))
      (node (ref "A1") (pin "3") (pinfunction "P$3_3") (pintype "power_in"))
      (node (ref "A2") (pin "3") (pinfunction "P$3_3") (pintype "power_in"))
      (node (ref "C1") (pin "1") (pinfunction "1_1") (pintype "passive"))
      (node (ref "C10") (pin "1") (pinfunction "1_1") (pintype "passive"))
      (node (ref "C11") (pin "-") (pinfunction "-_-") (pintype "passive"))
      (node (ref "C12") (pin "-") (pinfunction "-_-") (pintype "passive"))
      (node (ref "C13") (pin "1") (pinfunction "1_1") (pintype "passive"))
      (node (ref "C14") (pin "-") (pinfunction "-_-") (pintype "passive"))
      (node (ref "C15") (pin "1") (pinfunction "1_1") (pintype "passive"))
      (node (ref "C17") (pin "1") (pinfunction "1_1") (pintype "passive"))
      (node (ref "C19") (pin "2") (pinfunction "2_2") (pintype "passive"))
      (node (ref "C2") (pin "2") (pinfunction "2_2") (pintype "passive"))
      (node (ref "C22") (pin "1") (pinfunction "1_1") (pintype "passive"))
      (node (ref "C23") (pin "-") (pinfunction "-_-") (pintype "passive"))
      (node (ref "C3") (pin "2") (pinfunction "2_2") (pintype "passive"))
      (node (ref "C6") (pin "1") (pinfunction "1_1") (pintype "passive"))
      (node (ref "C7") (pin "1") (pinfunction "1_1") (pintype "passive"))
      (node (ref "C9") (pin "1") (pinfunction "1_1") (pintype "passive"))
      (node (ref "I2C") (pin "3") (pinfunction "3_3") (pintype "passive"))
      (node (ref "IC2") (pin "5") (pinfunction "GND_5") (pintype "power_in"))
      (node (ref "IC4") (pin "2") (pinfunction "GND_2") (pintype "passive"))
      (node (ref "IC4") (pin "2@1") (pinfunction "GND_2@1") (pintype "passive"))
      (node (ref "IC5") (pin "10") (pinfunction "VSS_10") (pintype "bidirectional"))
      (node (ref "IC6") (pin "1") (pinfunction "GND_1") (pintype "power_in"))
      (node (ref "IC7") (pin "2") (pinfunction "GND_2") (pintype "power_in"))
      (node (ref "Q1") (pin "2") (pinfunction "S_2") (pintype "passive"))
      (node (ref "Q2") (pin "2") (pinfunction "S_2") (pintype "passive"))
      (node (ref "R10") (pin "1") (pinfunction "1_1") (pintype "passive"))
      (node (ref "R13") (pin "2") (pinfunction "2_2") (pintype "passive"))
      (node (ref "R29") (pin "1") (pinfunction "1_1") (pintype "passive"))
      (node (ref "R33") (pin "2") (pinfunction "2_2") (pintype "passive"))
      (node (ref "R35") (pin "1") (pinfunction "1_1") (pintype "passive"))
      (node (ref "R49") (pin "2") (pinfunction "2_2") (pintype "passive"))
      (node (ref "R50") (pin "2") (pinfunction "2_2") (pintype "passive"))
      (node (ref "R51") (pin "2") (pinfunction "2_2") (pintype "passive"))
      (node (ref "R52") (pin "2") (pinfunction "2_2") (pintype "passive"))
      (node (ref "R53") (pin "2") (pinfunction "2_2") (pintype "passive"))
      (node (ref "R54") (pin "2") (pinfunction "2_2") (pintype "passive"))
      (node (ref "R55") (pin "2") (pinfunction "2_2") (pintype "passive"))
      (node (ref "R56") (pin "2") (pinfunction "2_2") (pintype "passive"))
      (node (ref "R57") (pin "2") (pinfunction "2_2") (pintype "passive"))
      (node (ref "R58") (pin "2") (pinfunction "2_2") (pintype "passive"))
      (node (ref "R59") (pin "2") (pinfunction "2_2") (pintype "passive"))
      (node (ref "R60") (pin "2") (pinfunction "2_2") (pintype "passive"))
      (node (ref "R61") (pin "2") (pinfunction "2_2") (pintype "passive"))
      (node (ref "R62") (pin "2") (pinfunction "2_2") (pintype "passive"))
      (node (ref "R63") (pin "2") (pinfunction "2_2") (pintype "passive"))
      (node (ref "R64") (pin "2") (pinfunction "2_2") (pintype "passive"))
      (node (ref "R66") (pin "2") (pinfunction "2_2") (pintype "passive"))
      (node (ref "R68") (pin "1") (pinfunction "1_1") (pintype "passive"))
      (node (ref "R70") (pin "2") (pinfunction "2_2") (pintype "passive"))
      (node (ref "R75") (pin "1") (pinfunction "1_1") (pintype "passive"))
      (node (ref "SWD") (pin "4") (pinfunction "4_4") (pintype "passive"))
      (node (ref "TVS1") (pin "A") (pinfunction "A_A") (pintype "passive"))
      (node (ref "TVS2") (pin "A") (pinfunction "A_A") (pintype "passive"))
      (node (ref "U2") (pin "23") (pinfunction "VSS_1_23") (pintype "power_in"))
      (node (ref "U2") (pin "35") (pinfunction "VSS_2_35") (pintype "power_in"))
      (node (ref "U2") (pin "47") (pinfunction "VSS_3_47") (pintype "power_in"))
      (node (ref "U2") (pin "8") (pinfunction "VSSA_8") (pintype "power_in"))
      (node (ref "UART") (pin "3") (pinfunction "3_3") (pintype "passive"))
      (node (ref "UART2") (pin "3") (pinfunction "3_3") (pintype "passive"))
      (node (ref "X0") (pin "14") (pinfunction "GND_14") (pintype "power_in"))
      (node (ref "X0") (pin "20") (pinfunction "GND_20") (pintype "power_in"))
      (node (ref "X0") (pin "25") (pinfunction "GND_25") (pintype "power_in"))
      (node (ref "X0") (pin "6") (pinfunction "GND_6") (pintype "power_in"))
      (node (ref "X0") (pin "9") (pinfunction "GND_9") (pintype "power_in"))
      (node (ref "X10") (pin "1") (pinfunction "KL_1") (pintype "passive"))
      (node (ref "X9") (pin "3") (pinfunction "KL_3") (pintype "passive"))
    )
    (net (code "43") (name "Net-(A0-P$1)") (class "Default")
      (node (ref "A0") (pin "2") (pinfunction "P$1_2") (pintype "bidirectional"))
      (node (ref "IC5") (pin "15") (pinfunction "A0_15") (pintype "bidirectional"))
    )
    (net (code "44") (name "Net-(A1-P$1)") (class "Default")
      (node (ref "A1") (pin "2") (pinfunction "P$1_2") (pintype "bidirectional"))
      (node (ref "IC5") (pin "16") (pinfunction "A1_16") (pintype "bidirectional"))
    )
    (net (code "45") (name "Net-(A2-P$1)") (class "Default")
      (node (ref "A2") (pin "2") (pinfunction "P$1_2") (pintype "bidirectional"))
      (node (ref "IC5") (pin "17") (pinfunction "A2_17") (pintype "bidirectional"))
    )
    (net (code "46") (name "Net-(IC2-A)") (class "Default")
      (node (ref "IC2") (pin "6") (pinfunction "A_6") (pintype "passive"))
      (node (ref "R9") (pin "1") (pinfunction "1_1") (pintype "passive"))
      (node (ref "TVS1") (pin "C") (pinfunction "C_C") (pintype "passive"))
      (node (ref "X10") (pin "2") (pinfunction "KL_2") (pintype "passive"))
    )
    (net (code "47") (name "Net-(IC2-B)") (class "Default")
      (node (ref "IC2") (pin "7") (pinfunction "B_7") (pintype "passive"))
      (node (ref "R9") (pin "2") (pinfunction "2_2") (pintype "passive"))
      (node (ref "TVS2") (pin "C") (pinfunction "C_C") (pintype "passive"))
      (node (ref "X10") (pin "3") (pinfunction "KL_3") (pintype "passive"))
    )
    (net (code "48") (name "Net-(IC3-VIN+)") (class "Default")
      (node (ref "C18") (pin "2") (pinfunction "2_2") (pintype "passive"))
      (node (ref "FB2") (pin "1") (pinfunction "1_1") (pintype "passive"))
      (node (ref "IC3") (pin "2") (pinfunction "VIN+_2") (pintype "bidirectional"))
    )
    (net (code "49") (name "Net-(IC3-VIN-)") (class "Default")
      (node (ref "C18") (pin "1") (pinfunction "1_1") (pintype "passive"))
      (node (ref "IC3") (pin "1") (pinfunction "VIN-_1") (pintype "bidirectional"))
      (node (ref "Q1") (pin "3") (pinfunction "D_3") (pintype "passive"))
    )
    (net (code "50") (name "Net-(IC3-VOUT+)") (class "Default")
      (node (ref "C16") (pin "1") (pinfunction "1_1") (pintype "passive"))
      (node (ref "IC3") (pin "4") (pinfunction "VOUT+_4") (pintype "bidirectional"))
      (node (ref "R17") (pin "2") (pinfunction "2_2") (pintype "passive"))
      (node (ref "R20") (pin "2") (pinfunction "2_2") (pintype "passive"))
      (node (ref "R25") (pin "2") (pinfunction "2_2") (pintype "passive"))
      (node (ref "R31") (pin "2") (pinfunction "2_2") (pintype "passive"))
      (node (ref "R37") (pin "2") (pinfunction "2_2") (pintype "passive"))
      (node (ref "R42") (pin "2") (pinfunction "2_2") (pintype "passive"))
      (node (ref "R45") (pin "2") (pinfunction "2_2") (pintype "passive"))
      (node (ref "R48") (pin "2") (pinfunction "2_2") (pintype "passive"))
      (node (ref "R65") (pin "1") (pinfunction "1_1") (pintype "passive"))
    )
    (net (code "51") (name "Net-(IC3-VOUT-)") (class "Default")
      (node (ref "C16") (pin "2") (pinfunction "2_2") (pintype "passive"))
      (node (ref "IC3") (pin "3") (pinfunction "VOUT-_3") (pintype "bidirectional"))
      (node (ref "OK1") (pin "2") (pinfunction "C_2") (pintype "passive"))
      (node (ref "OK1") (pin "4") (pinfunction "C_4") (pintype "passive"))
      (node (ref "OK2") (pin "2") (pinfunction "C_2") (pintype "passive"))
      (node (ref "OK2") (pin "4") (pinfunction "C_4") (pintype "passive"))
      (node (ref "OK3") (pin "2") (pinfunction "C_2") (pintype "passive"))
      (node (ref "OK3") (pin "4") (pinfunction "C_4") (pintype "passive"))
      (node (ref "OK4") (pin "2") (pinfunction "C_2") (pintype "passive"))
      (node (ref "OK4") (pin "4") (pinfunction "C_4") (pintype "passive"))
      (node (ref "OK5") (pin "2") (pinfunction "C_2") (pintype "passive"))
      (node (ref "OK5") (pin "4") (pinfunction "C_4") (pintype "passive"))
      (node (ref "OK6") (pin "2") (pinfunction "C_2") (pintype "passive"))
      (node (ref "OK6") (pin "4") (pinfunction "C_4") (pintype "passive"))
      (node (ref "OK7") (pin "2") (pinfunction "C_2") (pintype "passive"))
      (node (ref "OK7") (pin "4") (pinfunction "C_4") (pintype "passive"))
      (node (ref "OK8") (pin "2") (pinfunction "C_2") (pintype "passive"))
      (node (ref "OK8") (pin "4") (pinfunction "C_4") (pintype "passive"))
      (node (ref "OK9") (pin "2") (pinfunction "C_2") (pintype "passive"))
      (node (ref "TVS10") (pin "A") (pinfunction "A_A") (pintype "passive"))
      (node (ref "TVS11") (pin "A") (pinfunction "A_A") (pintype "passive"))
      (node (ref "TVS12") (pin "A") (pinfunction "A_A") (pintype "passive"))
      (node (ref "TVS13") (pin "A") (pinfunction "A_A") (pintype "passive"))
      (node (ref "TVS14") (pin "A") (pinfunction "A_A") (pintype "passive"))
      (node (ref "TVS15") (pin "A") (pinfunction "A_A") (pintype "passive"))
      (node (ref "TVS16") (pin "A") (pinfunction "A_A") (pintype "passive"))
      (node (ref "TVS17") (pin "A") (pinfunction "A_A") (pintype "passive"))
      (node (ref "TVS18") (pin "A") (pinfunction "A_A") (pintype "passive"))
      (node (ref "TVS3") (pin "A") (pinfunction "A_A") (pintype "passive"))
      (node (ref "TVS4") (pin "A") (pinfunction "A_A") (pintype "passive"))
      (node (ref "TVS5") (pin "A") (pinfunction "A_A") (pintype "passive"))
      (node (ref "TVS6") (pin "A") (pinfunction "A_A") (pintype "passive"))
      (node (ref "TVS7") (pin "A") (pinfunction "A_A") (pintype "passive"))
      (node (ref "TVS8") (pin "A") (pinfunction "A_A") (pintype "passive"))
      (node (ref "TVS9") (pin "A") (pinfunction "A_A") (pintype "passive"))
    )
    (net (code "52") (name "Net-(IC5-INTA)") (class "Default")
      (node (ref "IC5") (pin "19") (pinfunction "INTA_19") (pintype "bidirectional"))
      (node (ref "X0") (pin "26") (pinfunction "SIM_DET/PA_EINT10/PA10_26") (pintype "bidirectional"))
    )
    (net (code "53") (name "Net-(IC6-BST)") (class "Default")
      (node (ref "C8") (pin "1") (pinfunction "1_1") (pintype "passive"))
      (node (ref "IC6") (pin "6") (pinfunction "BST_6") (pintype "input"))
    )
    (net (code "54") (name "Net-(IC6-FB)") (class "Default")
      (node (ref "IC6") (pin "4") (pinfunction "FB_4") (pintype "input"))
      (node (ref "R10") (pin "2") (pinfunction "2_2") (pintype "passive"))
      (node (ref "R11") (pin "2") (pinfunction "2_2") (pintype "passive"))
    )
    (net (code "55") (name "Net-(IC6-SW)") (class "Default")
      (node (ref "C8") (pin "2") (pinfunction "2_2") (pintype "passive"))
      (node (ref "IC6") (pin "2") (pinfunction "SW_2") (pintype "passive"))
      (node (ref "L4.7") (pin "P$1") (pinfunction "1_P$1") (pintype "passive"))
    )
    (net (code "56") (name "Net-(L4.7-2)") (class "Default")
      (node (ref "C14") (pin "+") (pinfunction "+_+") (pintype "passive"))
      (node (ref "C22") (pin "2") (pinfunction "2_2") (pintype "passive"))
      (node (ref "C9") (pin "2") (pinfunction "2_2") (pintype "passive"))
      (node (ref "L4.7") (pin "P$2") (pinfunction "2_P$2") (pintype "passive"))
      (node (ref "R11") (pin "1") (pinfunction "1_1") (pintype "passive"))
      (node (ref "R5") (pin "2") (pinfunction "2_2") (pintype "passive"))
      (node (ref "X0") (pin "2") (pinfunction "5V_2") (pintype "power_in"))
      (node (ref "X0") (pin "4") (pinfunction "5V_4") (pintype "power_in"))
    )
    (net (code "57") (name "Net-(LED1-PadC)") (class "Default")
      (node (ref "LED1") (pin "C") (pinfunction "C_C") (pintype "passive"))
      (node (ref "R22") (pin "1") (pinfunction "1_1") (pintype "passive"))
    )
    (net (code "58") (name "Net-(LED2-PadC)") (class "Default")
      (node (ref "LED2") (pin "C") (pinfunction "C_C") (pintype "passive"))
      (node (ref "R23") (pin "1") (pinfunction "1_1") (pintype "passive"))
    )
    (net (code "59") (name "Net-(OK1A-A)") (class "Default")
      (node (ref "OK1") (pin "1") (pinfunction "A_1") (pintype "passive"))
      (node (ref "R16") (pin "2") (pinfunction "2_2") (pintype "passive"))
    )
    (net (code "60") (name "Net-(OK1B-A)") (class "Default")
      (node (ref "OK1") (pin "3") (pinfunction "A_3") (pintype "passive"))
      (node (ref "R15") (pin "2") (pinfunction "2_2") (pintype "passive"))
    )
    (net (code "61") (name "Net-(OK2A-A)") (class "Default")
      (node (ref "OK2") (pin "1") (pinfunction "A_1") (pintype "passive"))
      (node (ref "R19") (pin "2") (pinfunction "2_2") (pintype "passive"))
    )
    (net (code "62") (name "Net-(OK2B-A)") (class "Default")
      (node (ref "OK2") (pin "3") (pinfunction "A_3") (pintype "passive"))
      (node (ref "R18") (pin "2") (pinfunction "2_2") (pintype "passive"))
    )
    (net (code "63") (name "Net-(OK3A-A)") (class "Default")
      (node (ref "OK3") (pin "1") (pinfunction "A_1") (pintype "passive"))
      (node (ref "R24") (pin "2") (pinfunction "2_2") (pintype "passive"))
    )
    (net (code "64") (name "Net-(OK3B-A)") (class "Default")
      (node (ref "OK3") (pin "3") (pinfunction "A_3") (pintype "passive"))
      (node (ref "R21") (pin "2") (pinfunction "2_2") (pintype "passive"))
    )
    (net (code "65") (name "Net-(OK4A-A)") (class "Default")
      (node (ref "OK4") (pin "1") (pinfunction "A_1") (pintype "passive"))
      (node (ref "R27") (pin "2") (pinfunction "2_2") (pintype "passive"))
    )
    (net (code "66") (name "Net-(OK4B-A)") (class "Default")
      (node (ref "OK4") (pin "3") (pinfunction "A_3") (pintype "passive"))
      (node (ref "R26") (pin "2") (pinfunction "2_2") (pintype "passive"))
    )
    (net (code "67") (name "Net-(OK5A-A)") (class "Default")
      (node (ref "OK5") (pin "1") (pinfunction "A_1") (pintype "passive"))
      (node (ref "R36") (pin "2") (pinfunction "2_2") (pintype "passive"))
    )
    (net (code "68") (name "Net-(OK5B-A)") (class "Default")
      (node (ref "OK5") (pin "3") (pinfunction "A_3") (pintype "passive"))
      (node (ref "R32") (pin "2") (pinfunction "2_2") (pintype "passive"))
    )
    (net (code "69") (name "Net-(OK6A-A)") (class "Default")
      (node (ref "OK6") (pin "1") (pinfunction "A_1") (pintype "passive"))
      (node (ref "R39") (pin "2") (pinfunction "2_2") (pintype "passive"))
    )
    (net (code "70") (name "Net-(OK6B-A)") (class "Default")
      (node (ref "OK6") (pin "3") (pinfunction "A_3") (pintype "passive"))
      (node (ref "R38") (pin "2") (pinfunction "2_2") (pintype "passive"))
    )
    (net (code "71") (name "Net-(OK7A-A)") (class "Default")
      (node (ref "OK7") (pin "1") (pinfunction "A_1") (pintype "passive"))
      (node (ref "R44") (pin "2") (pinfunction "2_2") (pintype "passive"))
    )
    (net (code "72") (name "Net-(OK7B-A)") (class "Default")
      (node (ref "OK7") (pin "3") (pinfunction "A_3") (pintype "passive"))
      (node (ref "R43") (pin "2") (pinfunction "2_2") (pintype "passive"))
    )
    (net (code "73") (name "Net-(OK8A-A)") (class "Default")
      (node (ref "OK8") (pin "1") (pinfunction "A_1") (pintype "passive"))
      (node (ref "R47") (pin "2") (pinfunction "2_2") (pintype "passive"))
    )
    (net (code "74") (name "Net-(OK8B-A)") (class "Default")
      (node (ref "OK8") (pin "3") (pinfunction "A_3") (pintype "passive"))
      (node (ref "R46") (pin "2") (pinfunction "2_2") (pintype "passive"))
    )
    (net (code "75") (name "Net-(OK9A-A)") (class "Default")
      (node (ref "OK9") (pin "1") (pinfunction "A_1") (pintype "passive"))
      (node (ref "R65") (pin "2") (pinfunction "2_2") (pintype "passive"))
    )
    (net (code "76") (name "Net-(Q1-G)") (class "Default")
      (node (ref "Q1") (pin "1") (pinfunction "G_1") (pintype "passive"))
      (node (ref "R67") (pin "1") (pinfunction "1_1") (pintype "passive"))
    )
    (net (code "77") (name "Net-(Q2-D)") (class "Default")
      (node (ref "Q2") (pin "3") (pinfunction "D_3") (pintype "passive"))
      (node (ref "R28") (pin "1") (pinfunction "1_1") (pintype "passive"))
    )
    (net (code "78") (name "Net-(Q2-G)") (class "Default")
      (node (ref "Q2") (pin "1") (pinfunction "G_1") (pintype "passive"))
      (node (ref "R71") (pin "2") (pinfunction "2_2") (pintype "passive"))
    )
    (net (code "79") (name "Net-(U2-VBAT)") (class "Default")
      (node (ref "C2") (pin "1") (pinfunction "1_1") (pintype "passive"))
      (node (ref "FB1") (pin "2") (pinfunction "2_2") (pintype "passive"))
      (node (ref "U2") (pin "1") (pinfunction "VBAT_1") (pintype "power_in"))
      (node (ref "U2") (pin "9") (pinfunction "VDDA_9") (pintype "power_in"))
    )
    (net (code "80") (name "Net-(X0-PWM1{slash}PA06)") (class "Default")
      (node (ref "R70") (pin "1") (pinfunction "1_1") (pintype "passive"))
      (node (ref "R71") (pin "1") (pinfunction "1_1") (pintype "passive"))
      (node (ref "X0") (pin "7") (pinfunction "PWM1/PA06_7") (pintype "bidirectional"))
    )
    (net (code "81") (name "Net-(X0-UART1_RX{slash}PG07)") (class "Default")
      (node (ref "R1") (pin "2") (pinfunction "2_2") (pintype "passive"))
      (node (ref "R3") (pin "2") (pinfunction "2_2") (pintype "passive"))
      (node (ref "UART") (pin "2") (pinfunction "2_2") (pintype "passive"))
      (node (ref "X0") (pin "10") (pinfunction "UART1_RX/PG07_10") (pintype "bidirectional"))
    )
    (net (code "82") (name "Net-(X0-UART1_TX{slash}PG06)") (class "Default")
      (node (ref "R2") (pin "2") (pinfunction "2_2") (pintype "passive"))
      (node (ref "R4") (pin "2") (pinfunction "2_2") (pintype "passive"))
      (node (ref "UART") (pin "1") (pinfunction "1_1") (pintype "passive"))
      (node (ref "X0") (pin "8") (pinfunction "UART1_TX/PG06_8") (pintype "bidirectional"))
    )
    (net (code "83") (name "Net-(X0-UART2_RX{slash}PA01)") (class "Default")
      (node (ref "UART2") (pin "2") (pinfunction "2_2") (pintype "passive"))
      (node (ref "X0") (pin "11") (pinfunction "UART2_RX/PA01_11") (pintype "bidirectional"))
    )
    (net (code "84") (name "Net-(X0-UART2_TX{slash}PA00)") (class "Default")
      (node (ref "UART2") (pin "1") (pinfunction "1_1") (pintype "passive"))
      (node (ref "X0") (pin "13") (pinfunction "UART2_TX/PA00_13") (pintype "bidirectional"))
    )
    (net (code "85") (name "Net-(X1A-KL)") (class "Default")
      (node (ref "R21") (pin "1") (pinfunction "1_1") (pintype "passive"))
      (node (ref "TVS7") (pin "C") (pinfunction "C_C") (pintype "passive"))
      (node (ref "X1") (pin "1") (pinfunction "KL_1") (pintype "passive"))
    )
    (net (code "86") (name "Net-(X1B-KL)") (class "Default")
      (node (ref "R24") (pin "1") (pinfunction "1_1") (pintype "passive"))
      (node (ref "TVS8") (pin "C") (pinfunction "C_C") (pintype "passive"))
      (node (ref "X1") (pin "2") (pinfunction "KL_2") (pintype "passive"))
    )
    (net (code "87") (name "Net-(X1C-KL)") (class "Default")
      (node (ref "R25") (pin "1") (pinfunction "1_1") (pintype "passive"))
      (node (ref "X1") (pin "3") (pinfunction "KL_3") (pintype "passive"))
    )
    (net (code "88") (name "Net-(X2A-KL)") (class "Default")
      (node (ref "R43") (pin "1") (pinfunction "1_1") (pintype "passive"))
      (node (ref "TVS15") (pin "C") (pinfunction "C_C") (pintype "passive"))
      (node (ref "X2") (pin "1") (pinfunction "KL_1") (pintype "passive"))
    )
    (net (code "89") (name "Net-(X2B-KL)") (class "Default")
      (node (ref "R44") (pin "1") (pinfunction "1_1") (pintype "passive"))
      (node (ref "TVS16") (pin "C") (pinfunction "C_C") (pintype "passive"))
      (node (ref "X2") (pin "2") (pinfunction "KL_2") (pintype "passive"))
    )
    (net (code "90") (name "Net-(X2C-KL)") (class "Default")
      (node (ref "R45") (pin "1") (pinfunction "1_1") (pintype "passive"))
      (node (ref "X2") (pin "3") (pinfunction "KL_3") (pintype "passive"))
    )
    (net (code "91") (name "Net-(X3A-KL)") (class "Default")
      (node (ref "R38") (pin "1") (pinfunction "1_1") (pintype "passive"))
      (node (ref "TVS13") (pin "C") (pinfunction "C_C") (pintype "passive"))
      (node (ref "X3") (pin "1") (pinfunction "KL_1") (pintype "passive"))
    )
    (net (code "92") (name "Net-(X3B-KL)") (class "Default")
      (node (ref "R39") (pin "1") (pinfunction "1_1") (pintype "passive"))
      (node (ref "TVS14") (pin "C") (pinfunction "C_C") (pintype "passive"))
      (node (ref "X3") (pin "2") (pinfunction "KL_2") (pintype "passive"))
    )
    (net (code "93") (name "Net-(X3C-KL)") (class "Default")
      (node (ref "R42") (pin "1") (pinfunction "1_1") (pintype "passive"))
      (node (ref "X3") (pin "3") (pinfunction "KL_3") (pintype "passive"))
    )
    (net (code "94") (name "Net-(X4A-KL)") (class "Default")
      (node (ref "R15") (pin "1") (pinfunction "1_1") (pintype "passive"))
      (node (ref "TVS3") (pin "C") (pinfunction "C_C") (pintype "passive"))
      (node (ref "X4") (pin "1") (pinfunction "KL_1") (pintype "passive"))
    )
    (net (code "95") (name "Net-(X4B-KL)") (class "Default")
      (node (ref "R16") (pin "1") (pinfunction "1_1") (pintype "passive"))
      (node (ref "TVS4") (pin "C") (pinfunction "C_C") (pintype "passive"))
      (node (ref "X4") (pin "2") (pinfunction "KL_2") (pintype "passive"))
    )
    (net (code "96") (name "Net-(X4C-KL)") (class "Default")
      (node (ref "R17") (pin "1") (pinfunction "1_1") (pintype "passive"))
      (node (ref "X4") (pin "3") (pinfunction "KL_3") (pintype "passive"))
    )
    (net (code "97") (name "Net-(X5A-KL)") (class "Default")
      (node (ref "R26") (pin "1") (pinfunction "1_1") (pintype "passive"))
      (node (ref "TVS9") (pin "C") (pinfunction "C_C") (pintype "passive"))
      (node (ref "X5") (pin "1") (pinfunction "KL_1") (pintype "passive"))
    )
    (net (code "98") (name "Net-(X5B-KL)") (class "Default")
      (node (ref "R27") (pin "1") (pinfunction "1_1") (pintype "passive"))
      (node (ref "TVS10") (pin "C") (pinfunction "C_C") (pintype "passive"))
      (node (ref "X5") (pin "2") (pinfunction "KL_2") (pintype "passive"))
    )
    (net (code "99") (name "Net-(X5C-KL)") (class "Default")
      (node (ref "R31") (pin "1") (pinfunction "1_1") (pintype "passive"))
      (node (ref "X5") (pin "3") (pinfunction "KL_3") (pintype "passive"))
    )
    (net (code "100") (name "Net-(X6A-KL)") (class "Default")
      (node (ref "R46") (pin "1") (pinfunction "1_1") (pintype "passive"))
      (node (ref "TVS17") (pin "C") (pinfunction "C_C") (pintype "passive"))
      (node (ref "X6") (pin "1") (pinfunction "KL_1") (pintype "passive"))
    )
    (net (code "101") (name "Net-(X6B-KL)") (class "Default")
      (node (ref "R47") (pin "1") (pinfunction "1_1") (pintype "passive"))
      (node (ref "TVS18") (pin "C") (pinfunction "C_C") (pintype "passive"))
      (node (ref "X6") (pin "2") (pinfunction "KL_2") (pintype "passive"))
    )
    (net (code "102") (name "Net-(X6C-KL)") (class "Default")
      (node (ref "R48") (pin "1") (pinfunction "1_1") (pintype "passive"))
      (node (ref "X6") (pin "3") (pinfunction "KL_3") (pintype "passive"))
    )
    (net (code "103") (name "Net-(X7A-KL)") (class "Default")
      (node (ref "R18") (pin "1") (pinfunction "1_1") (pintype "passive"))
      (node (ref "TVS5") (pin "C") (pinfunction "C_C") (pintype "passive"))
      (node (ref "X7") (pin "1") (pinfunction "KL_1") (pintype "passive"))
    )
    (net (code "104") (name "Net-(X7B-KL)") (class "Default")
      (node (ref "R19") (pin "1") (pinfunction "1_1") (pintype "passive"))
      (node (ref "TVS6") (pin "C") (pinfunction "C_C") (pintype "passive"))
      (node (ref "X7") (pin "2") (pinfunction "KL_2") (pintype "passive"))
    )
    (net (code "105") (name "Net-(X7C-KL)") (class "Default")
      (node (ref "R20") (pin "1") (pinfunction "1_1") (pintype "passive"))
      (node (ref "X7") (pin "3") (pinfunction "KL_3") (pintype "passive"))
    )
    (net (code "106") (name "Net-(X8A-KL)") (class "Default")
      (node (ref "R32") (pin "1") (pinfunction "1_1") (pintype "passive"))
      (node (ref "TVS11") (pin "C") (pinfunction "C_C") (pintype "passive"))
      (node (ref "X8") (pin "1") (pinfunction "KL_1") (pintype "passive"))
    )
    (net (code "107") (name "Net-(X8B-KL)") (class "Default")
      (node (ref "R36") (pin "1") (pinfunction "1_1") (pintype "passive"))
      (node (ref "TVS12") (pin "C") (pinfunction "C_C") (pintype "passive"))
      (node (ref "X8") (pin "2") (pinfunction "KL_2") (pintype "passive"))
    )
    (net (code "108") (name "Net-(X8C-KL)") (class "Default")
      (node (ref "R37") (pin "1") (pinfunction "1_1") (pintype "passive"))
      (node (ref "X8") (pin "3") (pinfunction "KL_3") (pintype "passive"))
    )
    (net (code "109") (name "Net-(X9A-KL)") (class "Default")
      (node (ref "D10") (pin "A") (pinfunction "A_A") (pintype "passive"))
      (node (ref "R30") (pin "1") (pinfunction "1_1") (pintype "passive"))
      (node (ref "X9") (pin "1") (pinfunction "KL_1") (pintype "passive"))
    )
    (net (code "110") (name "Net-(X9B-KL)") (class "Default")
      (node (ref "D5") (pin "A") (pinfunction "A_A") (pintype "passive"))
      (node (ref "X9") (pin "2") (pinfunction "KL_2") (pintype "passive"))
    )
    (net (code "111") (name "Net-(X10D-KL)") (class "Default")
      (node (ref "C15") (pin "2") (pinfunction "2_2") (pintype "passive"))
      (node (ref "FS1") (pin "1") (pinfunction "1_1") (pintype "passive"))
      (node (ref "X10") (pin "4") (pinfunction "KL_4") (pintype "passive"))
    )
    (net (code "112") (name "unconnected-(IC5-NC-Pad11)") (class "Default")
      (node (ref "IC5") (pin "11") (pinfunction "NC_11") (pintype "bidirectional"))
    )
    (net (code "113") (name "unconnected-(IC5-NC-Pad14)") (class "Default")
      (node (ref "IC5") (pin "14") (pinfunction "NC_14") (pintype "bidirectional"))
    )
    (net (code "114") (name "unconnected-(IC7-NC-Pad3)") (class "Default")
      (node (ref "IC7") (pin "3") (pinfunction "NC_3") (pintype "no_connect"))
    )
    (net (code "115") (name "unconnected-(OK9B-A-Pad3)") (class "Default")
      (node (ref "OK9") (pin "3") (pinfunction "A_3") (pintype "passive"))
    )
    (net (code "116") (name "unconnected-(OK9B-C-Pad4)") (class "Default")
      (node (ref "OK9") (pin "4") (pinfunction "C_4") (pintype "passive"))
    )
    (net (code "117") (name "unconnected-(OK9B-COL-Pad6)") (class "Default")
      (node (ref "OK9") (pin "6") (pinfunction "COL_6") (pintype "passive"))
    )
    (net (code "118") (name "unconnected-(OK9B-EMIT-Pad5)") (class "Default")
      (node (ref "OK9") (pin "5") (pinfunction "EMIT_5") (pintype "passive"))
    )
    (net (code "119") (name "unconnected-(U2-BOOT0-Pad44)") (class "Default")
      (node (ref "U2") (pin "44") (pinfunction "BOOT0_44") (pintype "input"))
    )
    (net (code "120") (name "unconnected-(U2-PA4-Pad14)") (class "Default")
      (node (ref "U2") (pin "14") (pinfunction "PA4_14") (pintype "bidirectional"))
    )
    (net (code "121") (name "unconnected-(U2-PA5-Pad15)") (class "Default")
      (node (ref "U2") (pin "15") (pinfunction "PA5_15") (pintype "bidirectional"))
    )
    (net (code "122") (name "unconnected-(U2-PA6-Pad16)") (class "Default")
      (node (ref "U2") (pin "16") (pinfunction "PA6_16") (pintype "bidirectional"))
    )
    (net (code "123") (name "unconnected-(U2-PA7-Pad17)") (class "Default")
      (node (ref "U2") (pin "17") (pinfunction "PA7_17") (pintype "bidirectional"))
    )
    (net (code "124") (name "unconnected-(U2-PA8-Pad29)") (class "Default")
      (node (ref "U2") (pin "29") (pinfunction "PA8_29") (pintype "bidirectional"))
    )
    (net (code "125") (name "unconnected-(U2-PA11-Pad32)") (class "Default")
      (node (ref "U2") (pin "32") (pinfunction "PA11_32") (pintype "bidirectional"))
    )
    (net (code "126") (name "unconnected-(U2-PA12-Pad33)") (class "Default")
      (node (ref "U2") (pin "33") (pinfunction "PA12_33") (pintype "bidirectional"))
    )
    (net (code "127") (name "unconnected-(U2-PB0-Pad18)") (class "Default")
      (node (ref "U2") (pin "18") (pinfunction "PB0_18") (pintype "bidirectional"))
    )
    (net (code "128") (name "unconnected-(U2-PB1-Pad19)") (class "Default")
      (node (ref "U2") (pin "19") (pinfunction "PB1_19") (pintype "bidirectional"))
    )
    (net (code "129") (name "unconnected-(U2-PB12-Pad25)") (class "Default")
      (node (ref "U2") (pin "25") (pinfunction "PB12_25") (pintype "bidirectional"))
    )
    (net (code "130") (name "unconnected-(U2-PB14-Pad27)") (class "Default")
      (node (ref "U2") (pin "27") (pinfunction "PB14_27") (pintype "bidirectional"))
    )
    (net (code "131") (name "unconnected-(U2-PC13-TAMPER-RTC-Pad2)") (class "Default")
      (node (ref "U2") (pin "2") (pinfunction "PC13-TAMPER-RTC_2") (pintype "bidirectional"))
    )
    (net (code "132") (name "unconnected-(U2-PC14-OSC32_IN-Pad3)") (class "Default")
      (node (ref "U2") (pin "3") (pinfunction "PC14-OSC32_IN_3") (pintype "bidirectional"))
    )
    (net (code "133") (name "unconnected-(U2-PC15-OSC32_OUT-Pad4)") (class "Default")
      (node (ref "U2") (pin "4") (pinfunction "PC15-OSC32_OUT_4") (pintype "bidirectional"))
    )
    (net (code "134") (name "unconnected-(U2-PD0-OSC_IN-Pad5)") (class "Default")
      (node (ref "U2") (pin "5") (pinfunction "PD0-OSC_IN_5") (pintype "input"))
    )
    (net (code "135") (name "unconnected-(U2-PD1-OSC_OUT-Pad6)") (class "Default")
      (node (ref "U2") (pin "6") (pinfunction "PD1-OSC_OUT_6") (pintype "output"))
    )
    (net (code "136") (name "unconnected-(X0-PA13{slash}SPI1_CS-Pad24)") (class "Default")
      (node (ref "X0") (pin "24") (pinfunction "PA13/SPI1_CS_24") (pintype "bidirectional"))
    )
    (net (code "137") (name "unconnected-(X0-PA14{slash}SPI1_CLK-Pad23)") (class "Default")
      (node (ref "X0") (pin "23") (pinfunction "PA14/SPI1_CLK_23") (pintype "bidirectional"))
    )
    (net (code "138") (name "unconnected-(X0-PA15{slash}SPI1_MOSI-Pad19)") (class "Default")
      (node (ref "X0") (pin "19") (pinfunction "PA15/SPI1_MOSI_19") (pintype "bidirectional"))
    )
    (net (code "139") (name "unconnected-(X0-PA16{slash}SPI1_MISO-Pad21)") (class "Default")
      (node (ref "X0") (pin "21") (pinfunction "PA16/SPI1_MISO_21") (pintype "bidirectional"))
    )
    (net (code "140") (name "unconnected-(X0-PA18{slash}TWI1_SCL-Pad18)") (class "Default")
      (node (ref "X0") (pin "18") (pinfunction "PA18/TWI1_SCL_18") (pintype "bidirectional"))
    )
    (net (code "141") (name "unconnected-(X0-PA19{slash}TWI1_SDA-Pad16)") (class "Default")
      (node (ref "X0") (pin "16") (pinfunction "PA19/TWI1_SDA_16") (pintype "bidirectional"))
    )
    (net (code "142") (name "unconnected-(X0-UART2_CTS{slash}PA03-Pad15)") (class "Default")
      (node (ref "X0") (pin "15") (pinfunction "UART2_CTS/PA03_15") (pintype "bidirectional"))
    )
    (net (code "143") (name "unconnected-(X0-UART2_RTS{slash}PA02-Pad22)") (class "Default")
      (node (ref "X0") (pin "22") (pinfunction "UART2_RTS/PA02_22") (pintype "bidirectional"))
    )
  )
)
